# TKeyboard_2021-06-17.net
KiCad netlist of a schematic drawn in EasyEDA
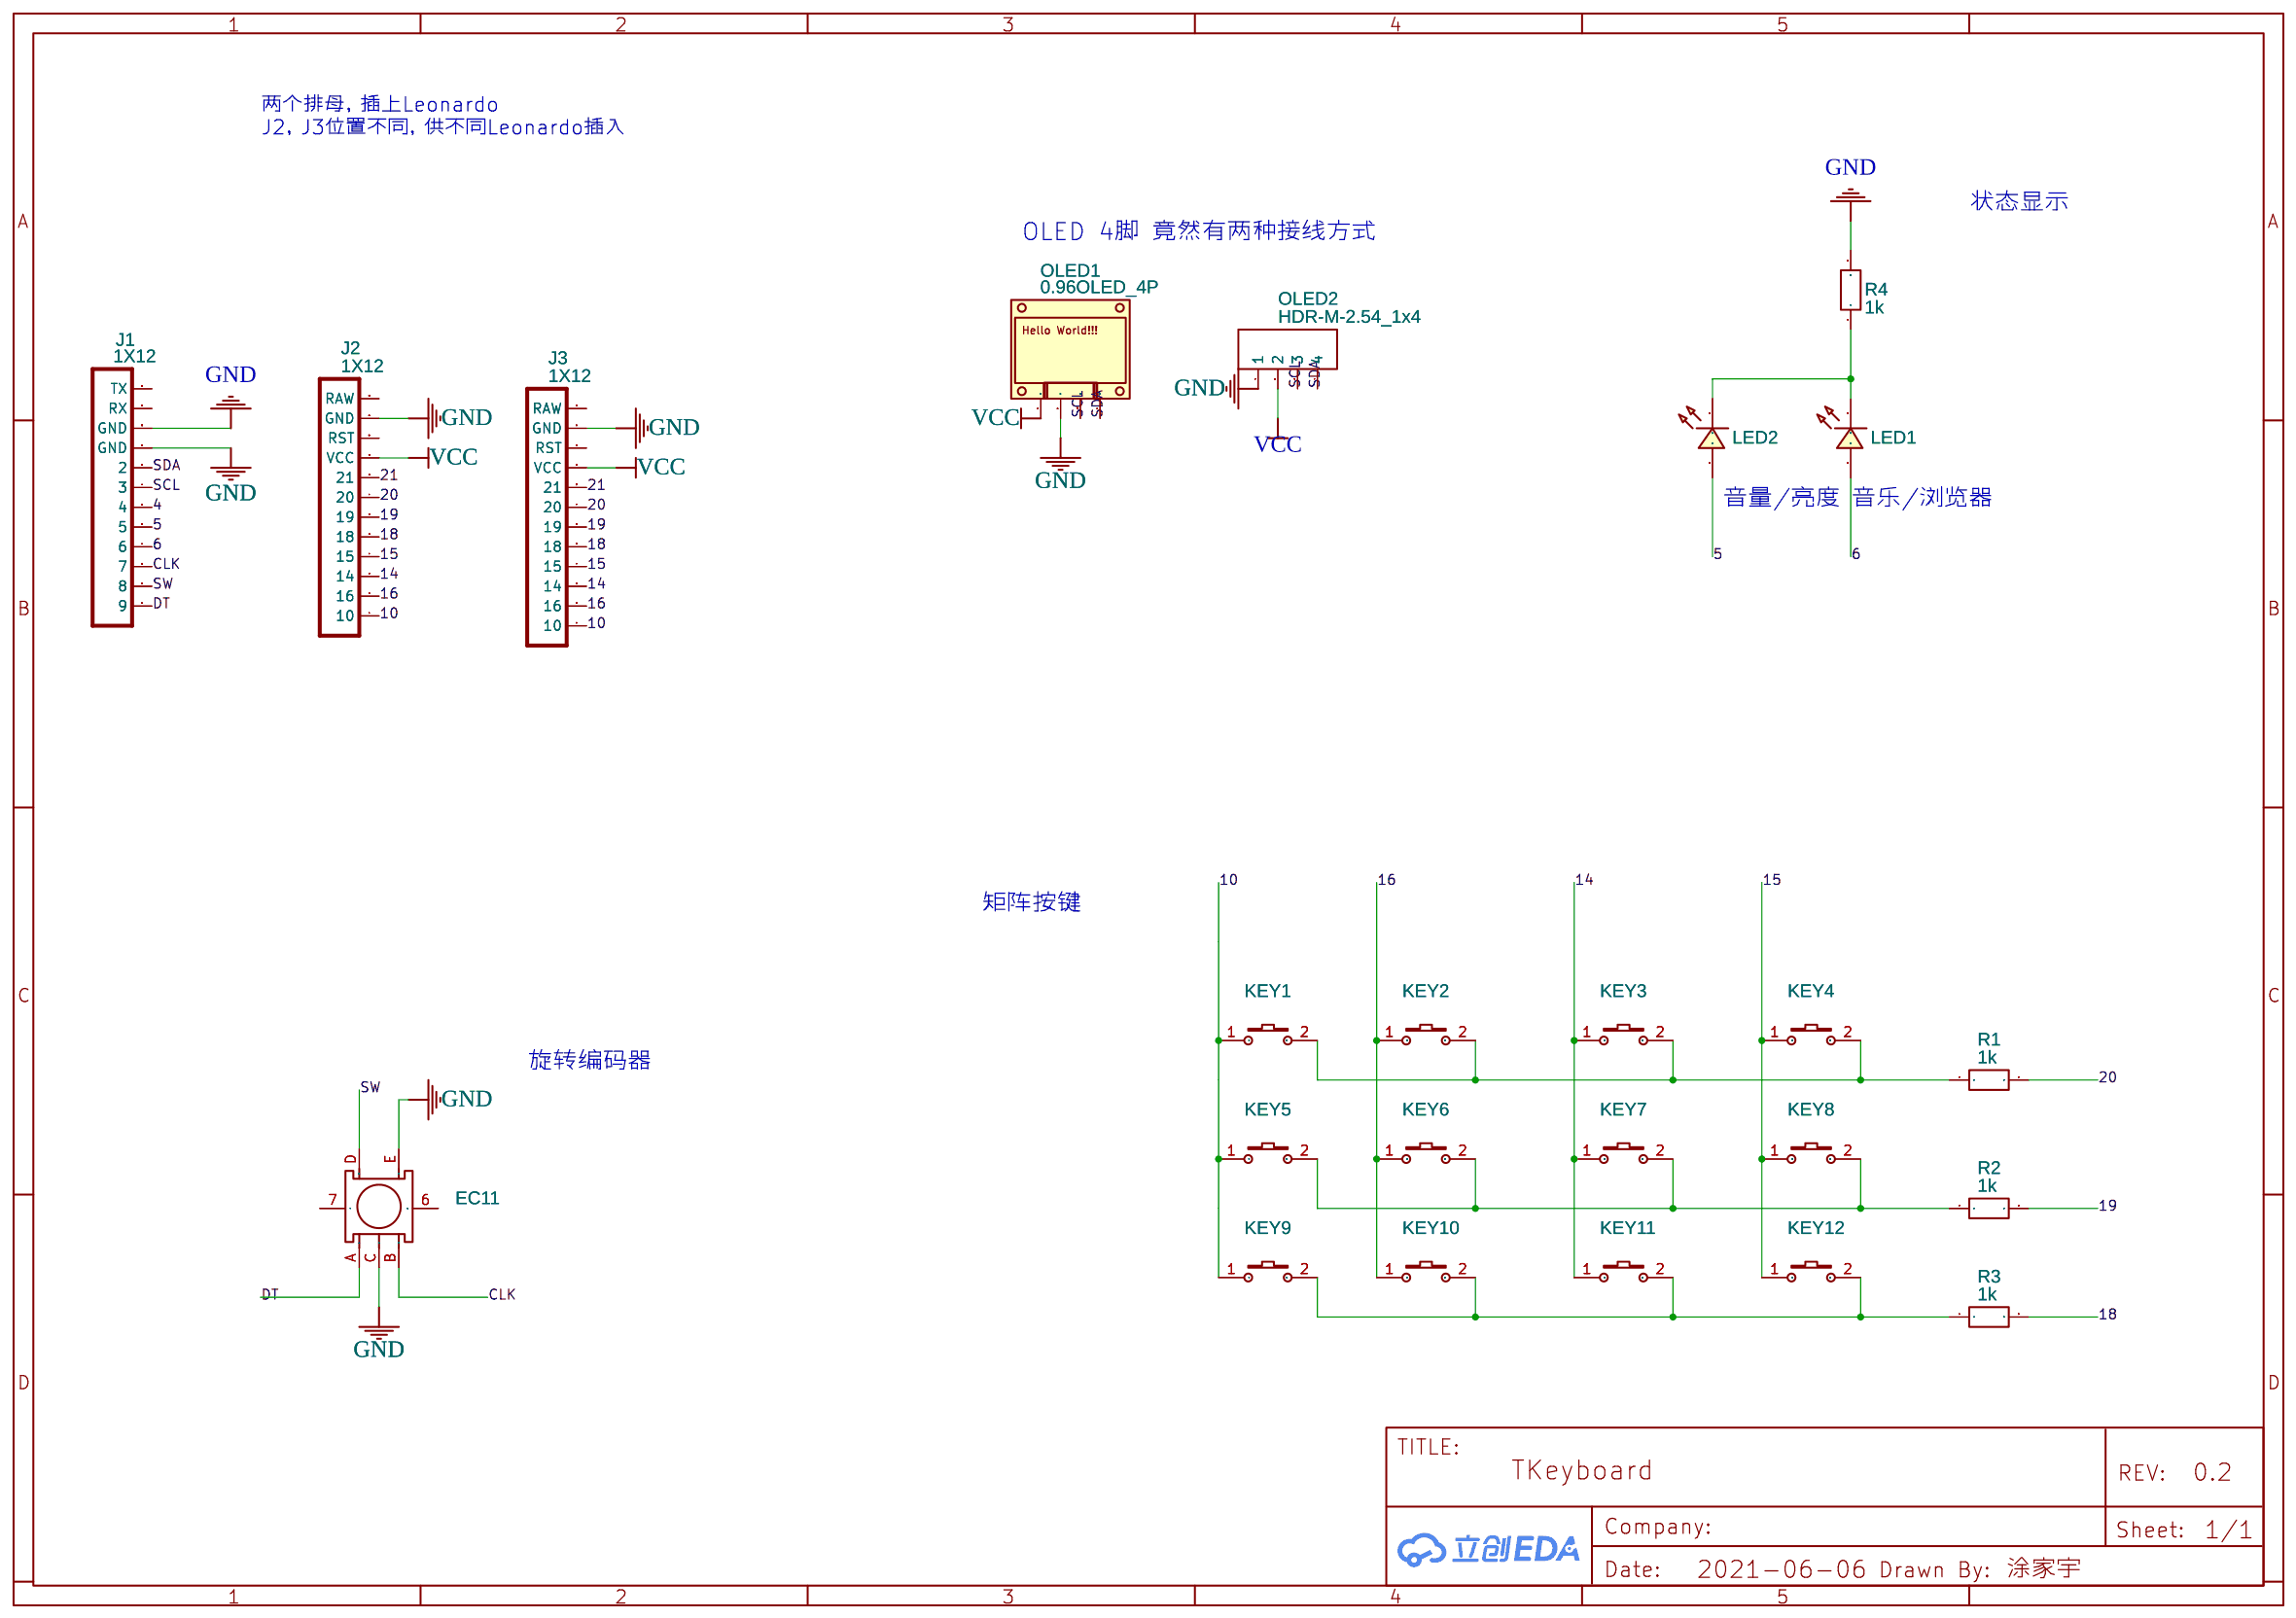
[diagram p0: schematic sheet]

(export (version "E")
  (design (tool "Eeschema 10.0.6"))
  (components
    (comp (ref "EC11")
      (value "EC11E152T409")
      (fields (field (name "BOM_Supplier Part") "C110314"))
      (libsource (lib "") (part "EC11E152T409"))
    )
    (comp (ref "J1") (value "1X12") (libsource (lib "") (part "1X12")))
    (comp (ref "J2") (value "1X12") (libsource (lib "") (part "1X12_1")))
    (comp (ref "J3") (value "1X12") (libsource (lib "") (part "1X12_1")))
    (comp (ref "KEY1")
      (value "K2-3.6×6.1_SMD")
      (fields
        (field (name "BOM_Manufacturer Part") "K2-1107ST-A4SW-06")
        (field (name "BOM_Supplier Part") "C118141")
      )
      (libsource (lib "") (part "K2-3.6×6.1_SMD"))
    )
    (comp (ref "KEY2")
      (value "K2-3.6×6.1_SMD")
      (fields
        (field (name "BOM_Manufacturer Part") "K2-1107ST-A4SW-06")
        (field (name "BOM_Supplier Part") "C118141")
      )
      (libsource (lib "") (part "K2-3.6×6.1_SMD"))
    )
    (comp (ref "KEY3")
      (value "K2-3.6×6.1_SMD")
      (fields
        (field (name "BOM_Manufacturer Part") "K2-1107ST-A4SW-06")
        (field (name "BOM_Supplier Part") "C118141")
      )
      (libsource (lib "") (part "K2-3.6×6.1_SMD"))
    )
    (comp (ref "KEY4")
      (value "K2-3.6×6.1_SMD")
      (fields
        (field (name "BOM_Manufacturer Part") "K2-1107ST-A4SW-06")
        (field (name "BOM_Supplier Part") "C118141")
      )
      (libsource (lib "") (part "K2-3.6×6.1_SMD"))
    )
    (comp (ref "KEY5")
      (value "K2-3.6×6.1_SMD")
      (fields
        (field (name "BOM_Manufacturer Part") "K2-1107ST-A4SW-06")
        (field (name "BOM_Supplier Part") "C118141")
      )
      (libsource (lib "") (part "K2-3.6×6.1_SMD"))
    )
    (comp (ref "KEY6")
      (value "K2-3.6×6.1_SMD")
      (fields
        (field (name "BOM_Manufacturer Part") "K2-1107ST-A4SW-06")
        (field (name "BOM_Supplier Part") "C118141")
      )
      (libsource (lib "") (part "K2-3.6×6.1_SMD"))
    )
    (comp (ref "KEY7")
      (value "K2-3.6×6.1_SMD")
      (fields
        (field (name "BOM_Manufacturer Part") "K2-1107ST-A4SW-06")
        (field (name "BOM_Supplier Part") "C118141")
      )
      (libsource (lib "") (part "K2-3.6×6.1_SMD"))
    )
    (comp (ref "KEY8")
      (value "K2-3.6×6.1_SMD")
      (fields
        (field (name "BOM_Manufacturer Part") "K2-1107ST-A4SW-06")
        (field (name "BOM_Supplier Part") "C118141")
      )
      (libsource (lib "") (part "K2-3.6×6.1_SMD"))
    )
    (comp (ref "KEY9")
      (value "K2-3.6×6.1_SMD")
      (fields
        (field (name "BOM_Manufacturer Part") "K2-1107ST-A4SW-06")
        (field (name "BOM_Supplier Part") "C118141")
      )
      (libsource (lib "") (part "K2-3.6×6.1_SMD"))
    )
    (comp (ref "KEY10")
      (value "K2-3.6×6.1_SMD")
      (fields
        (field (name "BOM_Manufacturer Part") "K2-1107ST-A4SW-06")
        (field (name "BOM_Supplier Part") "C118141")
      )
      (libsource (lib "") (part "K2-3.6×6.1_SMD"))
    )
    (comp (ref "KEY11")
      (value "K2-3.6×6.1_SMD")
      (fields
        (field (name "BOM_Manufacturer Part") "K2-1107ST-A4SW-06")
        (field (name "BOM_Supplier Part") "C118141")
      )
      (libsource (lib "") (part "K2-3.6×6.1_SMD"))
    )
    (comp (ref "KEY12")
      (value "K2-3.6×6.1_SMD")
      (fields
        (field (name "BOM_Manufacturer Part") "K2-1107ST-A4SW-06")
        (field (name "BOM_Supplier Part") "C118141")
      )
      (libsource (lib "") (part "K2-3.6×6.1_SMD"))
    )
    (comp (ref "LED1")
      (value "LED-0603_R")
      (fields
        (field (name "BOM_Manufacturer Part") "19-217/R6C-AL1M2VY/3T")
        (field (name "BOM_Supplier Part") "C72044")
      )
      (libsource (lib "") (part "LED-0603_R"))
    )
    (comp (ref "LED2")
      (value "LED-0603_R")
      (fields
        (field (name "BOM_Manufacturer Part") "19-217/R6C-AL1M2VY/3T")
        (field (name "BOM_Supplier Part") "C72044")
      )
      (libsource (lib "") (part "LED-0603_R"))
    )
    (comp (ref "OLED1") (value "0.96OLED_4P") (libsource (lib "") (part "0.96OLED_4P")))
    (comp (ref "OLED2")
      (value "HDR-M-2.54_1x4")
      (fields (field (name "BOM_Supplier Part") "C124378"))
      (libsource (lib "") (part "HDR-M-2.54_1x4"))
    )
    (comp (ref "R1") (value "1k") (libsource (lib "") (part "R_0603_EU")))
    (comp (ref "R2") (value "1k") (libsource (lib "") (part "R_0603_EU")))
    (comp (ref "R3") (value "1k") (libsource (lib "") (part "R_0603_EU")))
    (comp (ref "R4") (value "1k") (libsource (lib "") (part "R_0603_EU_1")))
  )
  (nets
    (net (code "1") (name "/4") (class "Default")
      (node (ref "J1") (pin "6") (pinfunction "4_6") (pintype "unspecified"))
    )
    (net (code "2") (name "/5") (class "Default")
      (node (ref "J1") (pin "5") (pinfunction "5_5") (pintype "unspecified"))
      (node (ref "LED2") (pin "1") (pinfunction "1_1") (pintype "unspecified"))
    )
    (net (code "3") (name "/6") (class "Default")
      (node (ref "J1") (pin "4") (pinfunction "6_4") (pintype "unspecified"))
      (node (ref "LED1") (pin "1") (pinfunction "1_1") (pintype "unspecified"))
    )
    (net (code "4") (name "/10") (class "Default")
      (node (ref "J2") (pin "1") (pinfunction "10_1") (pintype "unspecified"))
      (node (ref "J3") (pin "1") (pinfunction "10_1") (pintype "unspecified"))
      (node (ref "KEY1") (pin "1") (pinfunction "1_1") (pintype "unspecified"))
      (node (ref "KEY5") (pin "1") (pinfunction "1_1") (pintype "unspecified"))
      (node (ref "KEY9") (pin "1") (pinfunction "1_1") (pintype "unspecified"))
    )
    (net (code "5") (name "/14") (class "Default")
      (node (ref "J2") (pin "3") (pinfunction "14_3") (pintype "unspecified"))
      (node (ref "J3") (pin "3") (pinfunction "14_3") (pintype "unspecified"))
      (node (ref "KEY11") (pin "1") (pinfunction "1_1") (pintype "unspecified"))
      (node (ref "KEY3") (pin "1") (pinfunction "1_1") (pintype "unspecified"))
      (node (ref "KEY7") (pin "1") (pinfunction "1_1") (pintype "unspecified"))
    )
    (net (code "6") (name "/15") (class "Default")
      (node (ref "J2") (pin "4") (pinfunction "15_4") (pintype "unspecified"))
      (node (ref "J3") (pin "4") (pinfunction "15_4") (pintype "unspecified"))
      (node (ref "KEY12") (pin "1") (pinfunction "1_1") (pintype "unspecified"))
      (node (ref "KEY4") (pin "1") (pinfunction "1_1") (pintype "unspecified"))
      (node (ref "KEY8") (pin "1") (pinfunction "1_1") (pintype "unspecified"))
    )
    (net (code "7") (name "/16") (class "Default")
      (node (ref "J2") (pin "2") (pinfunction "16_2") (pintype "unspecified"))
      (node (ref "J3") (pin "2") (pinfunction "16_2") (pintype "unspecified"))
      (node (ref "KEY10") (pin "1") (pinfunction "1_1") (pintype "unspecified"))
      (node (ref "KEY2") (pin "1") (pinfunction "1_1") (pintype "unspecified"))
      (node (ref "KEY6") (pin "1") (pinfunction "1_1") (pintype "unspecified"))
    )
    (net (code "8") (name "/18") (class "Default")
      (node (ref "J2") (pin "5") (pinfunction "18_5") (pintype "unspecified"))
      (node (ref "J3") (pin "5") (pinfunction "18_5") (pintype "unspecified"))
      (node (ref "R3") (pin "2") (pinfunction "2_2") (pintype "unspecified"))
    )
    (net (code "9") (name "/19") (class "Default")
      (node (ref "J2") (pin "6") (pinfunction "19_6") (pintype "unspecified"))
      (node (ref "J3") (pin "6") (pinfunction "19_6") (pintype "unspecified"))
      (node (ref "R2") (pin "2") (pinfunction "2_2") (pintype "unspecified"))
    )
    (net (code "10") (name "/20") (class "Default")
      (node (ref "J2") (pin "7") (pinfunction "20_7") (pintype "unspecified"))
      (node (ref "J3") (pin "7") (pinfunction "20_7") (pintype "unspecified"))
      (node (ref "R1") (pin "2") (pinfunction "2_2") (pintype "unspecified"))
    )
    (net (code "11") (name "/21") (class "Default")
      (node (ref "J2") (pin "8") (pinfunction "21_8") (pintype "unspecified"))
      (node (ref "J3") (pin "8") (pinfunction "21_8") (pintype "unspecified"))
    )
    (net (code "12") (name "/CLK") (class "Default")
      (node (ref "EC11") (pin "B") (pinfunction "B_B") (pintype "unspecified"))
      (node (ref "J1") (pin "3") (pinfunction "7_3") (pintype "unspecified"))
    )
    (net (code "13") (name "/DT") (class "Default")
      (node (ref "EC11") (pin "A") (pinfunction "A_A") (pintype "unspecified"))
      (node (ref "J1") (pin "1") (pinfunction "9_1") (pintype "unspecified"))
    )
    (net (code "14") (name "/SCL") (class "Default")
      (node (ref "J1") (pin "7") (pinfunction "3_7") (pintype "unspecified"))
      (node (ref "OLED1") (pin "3") (pinfunction "3_3") (pintype "unspecified"))
      (node (ref "OLED2") (pin "3") (pinfunction "3_3") (pintype "unspecified"))
    )
    (net (code "15") (name "/SDA") (class "Default")
      (node (ref "J1") (pin "8") (pinfunction "2_8") (pintype "unspecified"))
      (node (ref "OLED1") (pin "4") (pinfunction "4_4") (pintype "unspecified"))
      (node (ref "OLED2") (pin "4") (pinfunction "4_4") (pintype "unspecified"))
    )
    (net (code "16") (name "/SW") (class "Default")
      (node (ref "EC11") (pin "D") (pinfunction "D_D") (pintype "unspecified"))
      (node (ref "J1") (pin "2") (pinfunction "8_2") (pintype "unspecified"))
    )
    (net (code "17") (name "GND") (class "Default")
      (node (ref "EC11") (pin "C") (pinfunction "C_C") (pintype "unspecified"))
      (node (ref "EC11") (pin "E") (pinfunction "E_E") (pintype "unspecified"))
      (node (ref "J1") (pin "10") (pinfunction "GND_10") (pintype "unspecified"))
      (node (ref "J1") (pin "9") (pinfunction "GND_9") (pintype "unspecified"))
      (node (ref "J2") (pin "11") (pinfunction "GND_11") (pintype "unspecified"))
      (node (ref "J3") (pin "11") (pinfunction "GND_11") (pintype "unspecified"))
      (node (ref "OLED1") (pin "2") (pinfunction "2_2") (pintype "unspecified"))
      (node (ref "OLED2") (pin "1") (pinfunction "1_1") (pintype "unspecified"))
      (node (ref "R4") (pin "2") (pinfunction "2_2") (pintype "unspecified"))
    )
    (net (code "18") (name "Net-(KEY1-Pad2)") (class "Default")
      (node (ref "KEY1") (pin "2") (pinfunction "2_2") (pintype "unspecified"))
      (node (ref "KEY2") (pin "2") (pinfunction "2_2") (pintype "unspecified"))
      (node (ref "KEY3") (pin "2") (pinfunction "2_2") (pintype "unspecified"))
      (node (ref "KEY4") (pin "2") (pinfunction "2_2") (pintype "unspecified"))
      (node (ref "R1") (pin "1") (pinfunction "1_1") (pintype "unspecified"))
    )
    (net (code "19") (name "Net-(KEY5-Pad2)") (class "Default")
      (node (ref "KEY5") (pin "2") (pinfunction "2_2") (pintype "unspecified"))
      (node (ref "KEY6") (pin "2") (pinfunction "2_2") (pintype "unspecified"))
      (node (ref "KEY7") (pin "2") (pinfunction "2_2") (pintype "unspecified"))
      (node (ref "KEY8") (pin "2") (pinfunction "2_2") (pintype "unspecified"))
      (node (ref "R2") (pin "1") (pinfunction "1_1") (pintype "unspecified"))
    )
    (net (code "20") (name "Net-(KEY10-Pad2)") (class "Default")
      (node (ref "KEY10") (pin "2") (pinfunction "2_2") (pintype "unspecified"))
      (node (ref "KEY11") (pin "2") (pinfunction "2_2") (pintype "unspecified"))
      (node (ref "KEY12") (pin "2") (pinfunction "2_2") (pintype "unspecified"))
      (node (ref "KEY9") (pin "2") (pinfunction "2_2") (pintype "unspecified"))
      (node (ref "R3") (pin "1") (pinfunction "1_1") (pintype "unspecified"))
    )
    (net (code "21") (name "Net-(LED1-Pad2)") (class "Default")
      (node (ref "LED1") (pin "2") (pinfunction "2_2") (pintype "unspecified"))
      (node (ref "LED2") (pin "2") (pinfunction "2_2") (pintype "unspecified"))
      (node (ref "R4") (pin "1") (pinfunction "1_1") (pintype "unspecified"))
    )
    (net (code "22") (name "VCC") (class "Default")
      (node (ref "J2") (pin "9") (pinfunction "VCC_9") (pintype "unspecified"))
      (node (ref "J3") (pin "9") (pinfunction "VCC_9") (pintype "unspecified"))
      (node (ref "OLED1") (pin "1") (pinfunction "1_1") (pintype "unspecified"))
      (node (ref "OLED2") (pin "2") (pinfunction "2_2") (pintype "unspecified"))
    )
    (net (code "23") (name "unconnected-(EC11-Pad6)") (class "Default")
      (node (ref "EC11") (pin "6") (pinfunction "6_6") (pintype "unspecified"))
    )
    (net (code "24") (name "unconnected-(EC11-Pad7)") (class "Default")
      (node (ref "EC11") (pin "7") (pinfunction "7_7") (pintype "unspecified"))
    )
    (net (code "25") (name "unconnected-(J1-RX-Pad11)") (class "Default")
      (node (ref "J1") (pin "11") (pinfunction "RX_11") (pintype "unspecified"))
    )
    (net (code "26") (name "unconnected-(J1-TX-Pad12)") (class "Default")
      (node (ref "J1") (pin "12") (pinfunction "TX_12") (pintype "unspecified"))
    )
    (net (code "27") (name "unconnected-(J2-RAW-Pad12)") (class "Default")
      (node (ref "J2") (pin "12") (pinfunction "RAW_12") (pintype "unspecified"))
    )
    (net (code "28") (name "unconnected-(J2-RST-Pad10)") (class "Default")
      (node (ref "J2") (pin "10") (pinfunction "RST_10") (pintype "unspecified"))
    )
    (net (code "29") (name "unconnected-(J3-RAW-Pad12)") (class "Default")
      (node (ref "J3") (pin "12") (pinfunction "RAW_12") (pintype "unspecified"))
    )
    (net (code "30") (name "unconnected-(J3-RST-Pad10)") (class "Default")
      (node (ref "J3") (pin "10") (pinfunction "RST_10") (pintype "unspecified"))
    )
  )
)
